# TPT02rrrrrrr.net
KiCad netlist of a schematic drawn in EAGLE
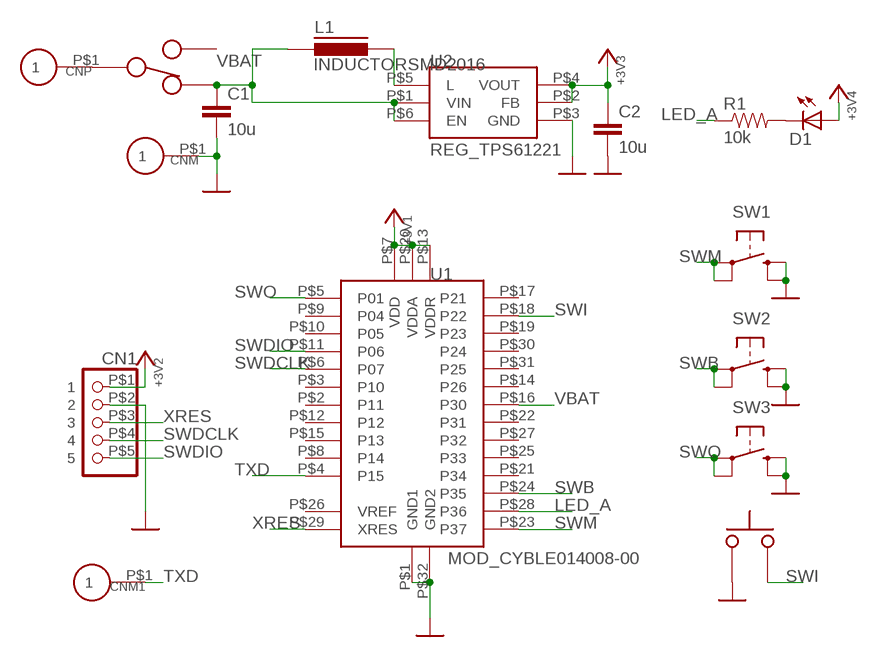
[diagram p0: schematic, sheet 1]

(export (version "E")
  (design (tool "Eeschema 10.0.6"))
  (components
    (comp (ref "C1")
      (value "10u")
      (footprint "eagle-import:0603")
      (libsource (lib "eagle-import") (part "CAP0603"))
    )
    (comp (ref "C2")
      (value "10u")
      (footprint "eagle-import:0603")
      (libsource (lib "eagle-import") (part "CAP0603"))
    )
    (comp (ref "CN1")
      (value "CON_PINHD-1X550MIL")
      (footprint "eagle-import:1X5_50MIL")
      (libsource (lib "eagle-import") (part "CON_PINHD-1X550MIL"))
    )
    (comp (ref "CNM")
      (value "CON_P01SMD1MM")
      (footprint "eagle-import:PAD_SMD1MM")
      (libsource (lib "eagle-import") (part "CON_P01SMD1MM"))
    )
    (comp (ref "CNM1")
      (value "CON_P01SMD1MM")
      (footprint "eagle-import:PAD_SMD1MM")
      (libsource (lib "eagle-import") (part "CON_P01SMD1MM"))
    )
    (comp (ref "CNP")
      (value "CON_P01SMD1MM")
      (footprint "eagle-import:PAD_SMD1MM")
      (libsource (lib "eagle-import") (part "CON_P01SMD1MM"))
    )
    (comp (ref "D1")
      (value "LED0603")
      (footprint "eagle-import:SPARKFUN_LED-0603")
      (libsource (lib "eagle-import") (part "LED0603"))
    )
    (comp (ref "L1")
      (value "INDUCTORSMD2016")
      (footprint "eagle-import:2016")
      (libsource (lib "eagle-import") (part "INDUCTORSMD2016"))
    )
    (comp (ref "R1")
      (value "10k")
      (footprint "eagle-import:0603")
      (libsource (lib "eagle-import") (part "RES0603"))
    )
    (comp (ref "SW1")
      (value "SW_TACTEVQP2")
      (footprint "eagle-import:SW_EVQP2")
      (libsource (lib "eagle-import") (part "SW_TACTEVQP2"))
    )
    (comp (ref "SW2")
      (value "SW_TACTEVQPLNA08NOGND")
      (footprint "eagle-import:SW_EVQPLBA08_NOGND")
      (libsource (lib "eagle-import") (part "SW_TACTEVQPLNA08NOGND"))
    )
    (comp (ref "SW3")
      (value "SW_TACTEVQPLNA08NOGND")
      (footprint "eagle-import:SW_EVQPLBA08_NOGND")
      (libsource (lib "eagle-import") (part "SW_TACTEVQPLNA08NOGND"))
    )
    (comp (ref "SW4")
      (value "SW_SLIDECUS12B")
      (footprint "eagle-import:SW_CUS-12B")
      (libsource (lib "eagle-import") (part "SW_SLIDECUS12B"))
    )
    (comp (ref "SW5")
      (value "SW_TACT2PB3U3000")
      (footprint "eagle-import:SW_B3U-3000P")
      (libsource (lib "eagle-import") (part "SW_TACT2PB3U3000"))
    )
    (comp (ref "U1")
      (value "MOD_CYBLE014008-00")
      (footprint "eagle-import:MOD_CYBLE014008-00")
      (libsource (lib "eagle-import") (part "MOD_CYBLE014008-00"))
    )
    (comp (ref "U2")
      (value "REG_TPS61221")
      (footprint "eagle-import:SC70-6")
      (libsource (lib "eagle-import") (part "REG_TPS61221"))
    )
  )
  (nets
    (net (code "1") (name "/LED_A") (class "Default")
      (node (ref "R1") (pin "1") (pinfunction "1_1") (pintype "passive"))
      (node (ref "U1") (pin "P$28") (pinfunction "P36_P$28") (pintype "bidirectional"))
    )
    (net (code "2") (name "/P$3") (class "Default")
      (node (ref "SW4") (pin "P$3") (pinfunction "P$3_P$3") (pintype "power_in"))
    )
    (net (code "3") (name "/SWB") (class "Default")
      (node (ref "SW2") (pin "A1") (pinfunction "P_A1") (pintype "passive"))
      (node (ref "SW2") (pin "A2") (pinfunction "P1_A2") (pintype "passive"))
      (node (ref "U1") (pin "P$24") (pinfunction "P35_P$24") (pintype "bidirectional"))
    )
    (net (code "4") (name "/SWDCLK") (class "Default")
      (node (ref "CN1") (pin "P$4") (pinfunction "4_P$4") (pintype "passive"))
      (node (ref "U1") (pin "P$6") (pinfunction "P07_P$6") (pintype "bidirectional"))
    )
    (net (code "5") (name "/SWDIO") (class "Default")
      (node (ref "CN1") (pin "P$5") (pinfunction "5_P$5") (pintype "passive"))
      (node (ref "U1") (pin "P$11") (pinfunction "P06_P$11") (pintype "bidirectional"))
    )
    (net (code "6") (name "/SWI") (class "Default")
      (node (ref "SW5") (pin "P$1") (pinfunction "P$1_P$1") (pintype "passive"))
      (node (ref "U1") (pin "P$18") (pinfunction "P22_P$18") (pintype "bidirectional"))
    )
    (net (code "7") (name "/SWM") (class "Default")
      (node (ref "SW1") (pin "PA1") (pinfunction "P_PA1") (pintype "passive"))
      (node (ref "SW1") (pin "PA2") (pinfunction "P1_PA2") (pintype "passive"))
      (node (ref "U1") (pin "P$23") (pinfunction "P37_P$23") (pintype "bidirectional"))
    )
    (net (code "8") (name "/SWO") (class "Default")
      (node (ref "SW3") (pin "A1") (pinfunction "P_A1") (pintype "passive"))
      (node (ref "SW3") (pin "A2") (pinfunction "P1_A2") (pintype "passive"))
      (node (ref "U1") (pin "P$5") (pinfunction "P01_P$5") (pintype "bidirectional"))
    )
    (net (code "9") (name "/TXD") (class "Default")
      (node (ref "CNM1") (pin "P$1") (pinfunction "1_P$1") (pintype "bidirectional"))
      (node (ref "U1") (pin "P$4") (pinfunction "P15_P$4") (pintype "bidirectional"))
    )
    (net (code "10") (name "/VBAT") (class "Default")
      (node (ref "C1") (pin "1") (pinfunction "1_1") (pintype "passive"))
      (node (ref "L1") (pin "P$1") (pinfunction "1_P$1") (pintype "passive"))
      (node (ref "SW4") (pin "P$1") (pinfunction "P$1_P$1") (pintype "power_in"))
      (node (ref "U1") (pin "P$16") (pinfunction "P30_P$16") (pintype "bidirectional"))
      (node (ref "U2") (pin "P$1") (pinfunction "VIN_P$1") (pintype "bidirectional"))
      (node (ref "U2") (pin "P$6") (pinfunction "EN_P$6") (pintype "bidirectional"))
    )
    (net (code "11") (name "/XRES") (class "Default")
      (node (ref "CN1") (pin "P$3") (pinfunction "3_P$3") (pintype "passive"))
      (node (ref "U1") (pin "P$29") (pinfunction "XRES_P$29") (pintype "bidirectional"))
    )
    (net (code "12") (name "Net-(CNP-1)") (class "Default")
      (node (ref "CNP") (pin "P$1") (pinfunction "1_P$1") (pintype "bidirectional"))
      (node (ref "SW4") (pin "P$2") (pinfunction "P$2_P$2") (pintype "power_in"))
    )
    (net (code "13") (name "Net-(D1-PadC)") (class "Default")
      (node (ref "D1") (pin "C") (pinfunction "C_C") (pintype "passive"))
      (node (ref "R1") (pin "2") (pinfunction "2_2") (pintype "passive"))
    )
    (net (code "14") (name "Net-(L1-2)") (class "Default")
      (node (ref "L1") (pin "P$2") (pinfunction "2_P$2") (pintype "passive"))
      (node (ref "U2") (pin "P$5") (pinfunction "L_P$5") (pintype "bidirectional"))
    )
    (net (code "15") (name "POW_+3V3") (class "Default")
      (node (ref "C2") (pin "1") (pinfunction "1_1") (pintype "passive"))
      (node (ref "CN1") (pin "P$1") (pinfunction "1_P$1") (pintype "passive"))
      (node (ref "D1") (pin "A") (pinfunction "A_A") (pintype "passive"))
      (node (ref "U1") (pin "P$13") (pinfunction "VDDR_P$13") (pintype "bidirectional"))
      (node (ref "U1") (pin "P$20") (pinfunction "VDDA_P$20") (pintype "bidirectional"))
      (node (ref "U1") (pin "P$7") (pinfunction "VDD_P$7") (pintype "bidirectional"))
      (node (ref "U2") (pin "P$2") (pinfunction "FB_P$2") (pintype "bidirectional"))
      (node (ref "U2") (pin "P$4") (pinfunction "VOUT_P$4") (pintype "bidirectional"))
    )
    (net (code "16") (name "POW_GND") (class "Default")
      (node (ref "C1") (pin "2") (pinfunction "2_2") (pintype "passive"))
      (node (ref "C2") (pin "2") (pinfunction "2_2") (pintype "passive"))
      (node (ref "CN1") (pin "P$2") (pinfunction "2_P$2") (pintype "passive"))
      (node (ref "CNM") (pin "P$1") (pinfunction "1_P$1") (pintype "bidirectional"))
      (node (ref "SW1") (pin "PB1") (pinfunction "S_PB1") (pintype "passive"))
      (node (ref "SW1") (pin "PB2") (pinfunction "S1_PB2") (pintype "passive"))
      (node (ref "SW2") (pin "B1") (pinfunction "S_B1") (pintype "passive"))
      (node (ref "SW2") (pin "B2") (pinfunction "S1_B2") (pintype "passive"))
      (node (ref "SW3") (pin "B1") (pinfunction "S_B1") (pintype "passive"))
      (node (ref "SW3") (pin "B2") (pinfunction "S1_B2") (pintype "passive"))
      (node (ref "SW5") (pin "P$2") (pinfunction "P$2_P$2") (pintype "passive"))
      (node (ref "U1") (pin "P$1") (pinfunction "GND1_P$1") (pintype "bidirectional"))
      (node (ref "U1") (pin "P$32") (pinfunction "GND2_P$32") (pintype "bidirectional"))
      (node (ref "U2") (pin "P$3") (pinfunction "GND_P$3") (pintype "bidirectional"))
    )
    (net (code "17") (name "unconnected-(U1-P04-PadP$9)") (class "Default")
      (node (ref "U1") (pin "P$9") (pinfunction "P04_P$9") (pintype "bidirectional"))
    )
    (net (code "18") (name "unconnected-(U1-P05-PadP$10)") (class "Default")
      (node (ref "U1") (pin "P$10") (pinfunction "P05_P$10") (pintype "bidirectional"))
    )
    (net (code "19") (name "unconnected-(U1-P10-PadP$3)") (class "Default")
      (node (ref "U1") (pin "P$3") (pinfunction "P10_P$3") (pintype "bidirectional"))
    )
    (net (code "20") (name "unconnected-(U1-P11-PadP$2)") (class "Default")
      (node (ref "U1") (pin "P$2") (pinfunction "P11_P$2") (pintype "bidirectional"))
    )
    (net (code "21") (name "unconnected-(U1-P12-PadP$12)") (class "Default")
      (node (ref "U1") (pin "P$12") (pinfunction "P12_P$12") (pintype "bidirectional"))
    )
    (net (code "22") (name "unconnected-(U1-P13-PadP$15)") (class "Default")
      (node (ref "U1") (pin "P$15") (pinfunction "P13_P$15") (pintype "bidirectional"))
    )
    (net (code "23") (name "unconnected-(U1-P14-PadP$8)") (class "Default")
      (node (ref "U1") (pin "P$8") (pinfunction "P14_P$8") (pintype "bidirectional"))
    )
    (net (code "24") (name "unconnected-(U1-P21-PadP$17)") (class "Default")
      (node (ref "U1") (pin "P$17") (pinfunction "P21_P$17") (pintype "bidirectional"))
    )
    (net (code "25") (name "unconnected-(U1-P23-PadP$19)") (class "Default")
      (node (ref "U1") (pin "P$19") (pinfunction "P23_P$19") (pintype "bidirectional"))
    )
    (net (code "26") (name "unconnected-(U1-P24-PadP$30)") (class "Default")
      (node (ref "U1") (pin "P$30") (pinfunction "P24_P$30") (pintype "bidirectional"))
    )
    (net (code "27") (name "unconnected-(U1-P25-PadP$31)") (class "Default")
      (node (ref "U1") (pin "P$31") (pinfunction "P25_P$31") (pintype "bidirectional"))
    )
    (net (code "28") (name "unconnected-(U1-P26-PadP$14)") (class "Default")
      (node (ref "U1") (pin "P$14") (pinfunction "P26_P$14") (pintype "bidirectional"))
    )
    (net (code "29") (name "unconnected-(U1-P31-PadP$22)") (class "Default")
      (node (ref "U1") (pin "P$22") (pinfunction "P31_P$22") (pintype "bidirectional"))
    )
    (net (code "30") (name "unconnected-(U1-P32-PadP$27)") (class "Default")
      (node (ref "U1") (pin "P$27") (pinfunction "P32_P$27") (pintype "bidirectional"))
    )
    (net (code "31") (name "unconnected-(U1-P33-PadP$25)") (class "Default")
      (node (ref "U1") (pin "P$25") (pinfunction "P33_P$25") (pintype "bidirectional"))
    )
    (net (code "32") (name "unconnected-(U1-P34-PadP$21)") (class "Default")
      (node (ref "U1") (pin "P$21") (pinfunction "P34_P$21") (pintype "bidirectional"))
    )
    (net (code "33") (name "unconnected-(U1-VREF-PadP$26)") (class "Default")
      (node (ref "U1") (pin "P$26") (pinfunction "VREF_P$26") (pintype "bidirectional"))
    )
  )
)
